# 1-Schematic_2-IRT-GR4-ColleJoulian.net
KiCad netlist of a schematic drawn in EasyEDA
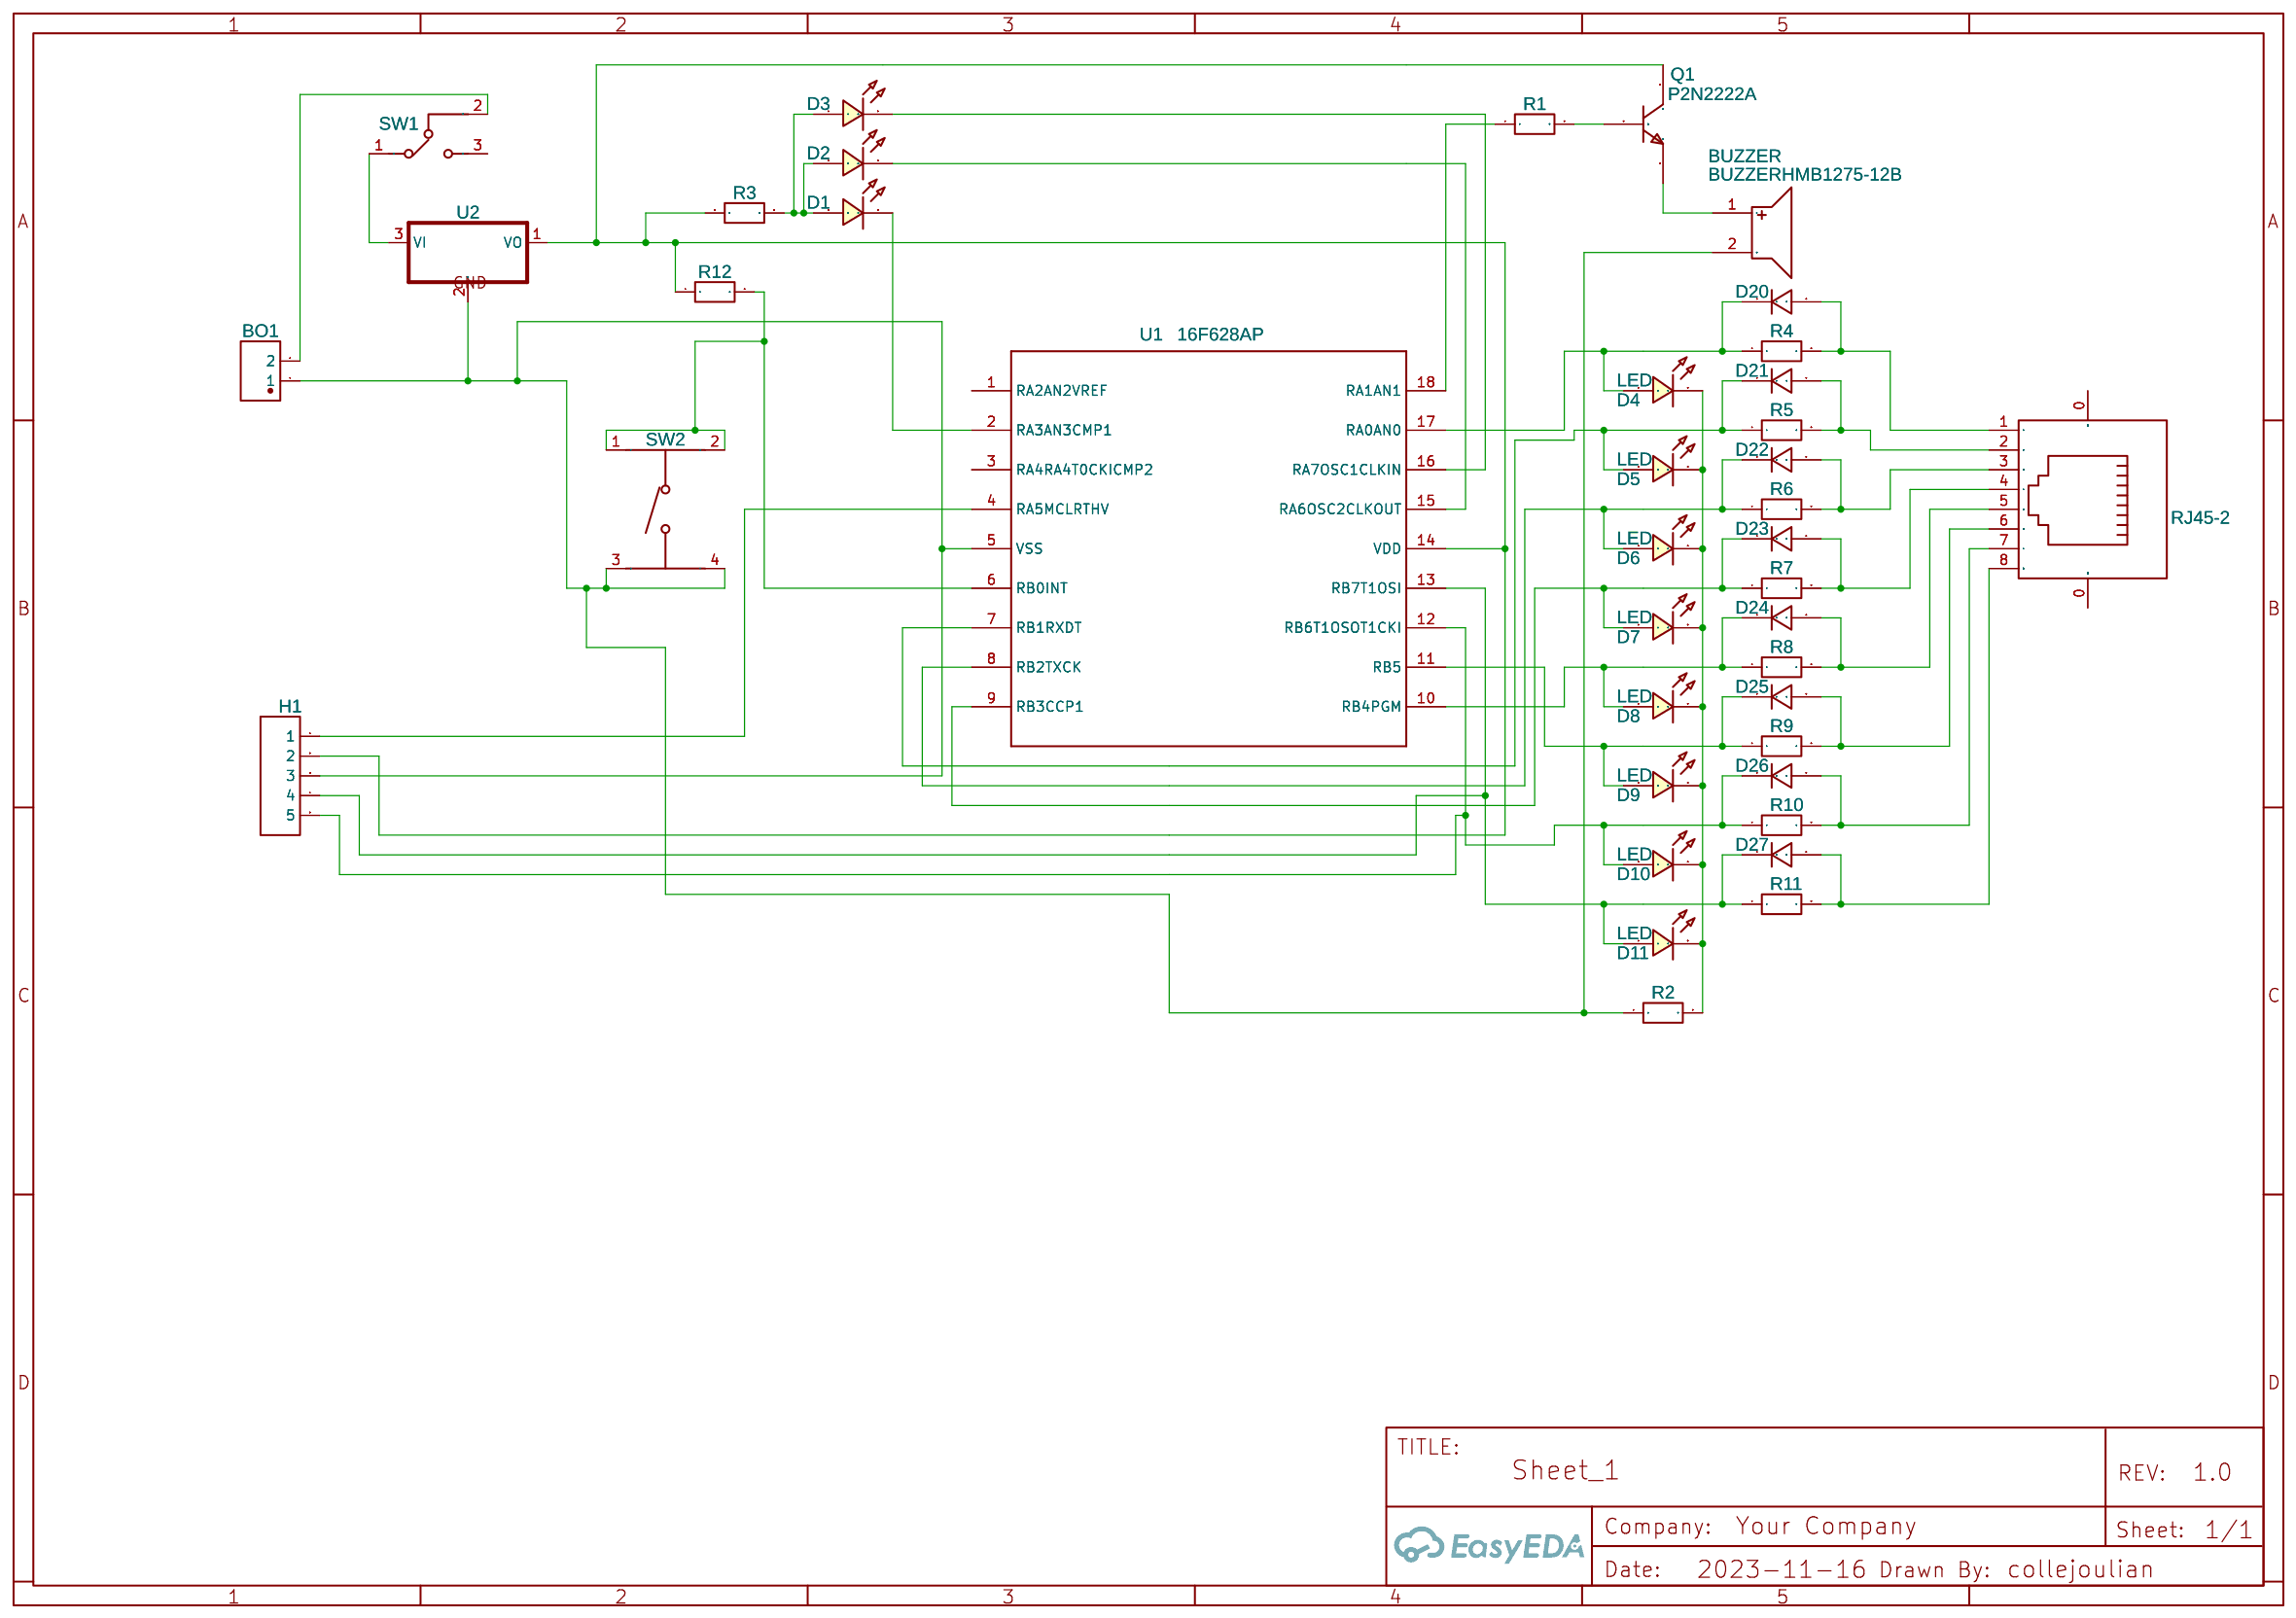
[diagram p0: schematic sheet]

(export (version "E")
  (design (tool "Eeschema 10.0.6"))
  (components
    (comp (ref "BO1")
      (value "BV-2P-5mm")
      (fields
        (field (name "Manufacturer Part") "KF301-5.0-2P")
        (field (name "Manufacturer") "Cixi Kefa Elec")
      )
      (libsource (lib "") (part "Bornier A Vis 2P - 5mm"))
    )
    (comp (ref "BUZZER")
      (value "BUZZERHMB1275-12B")
      (fields (field (name "Manufacturer Part") "buzzerHMB1275-12B") (field (name "Manufacturer") "HNDZ"))
      (libsource (lib "") (part "BUZZERHMB1275-12B"))
    )
    (comp (ref "D1")
      (value "D1")
      (fields
        (field (name "Manufacturer Part") "204-10SDRD/S530-A3-L")
        (field (name "Manufacturer") "EVERLIGHT(台湾亿光)")
      )
      (libsource (lib "") (part "LED-TH-3mm_R"))
    )
    (comp (ref "D2")
      (value "D2")
      (fields
        (field (name "Manufacturer Part") "204-10SDRD/S530-A3-L")
        (field (name "Manufacturer") "EVERLIGHT(台湾亿光)")
      )
      (libsource (lib "") (part "LED-TH-3mm_R"))
    )
    (comp (ref "D3")
      (value "D3")
      (fields
        (field (name "Manufacturer Part") "204-10SDRD/S530-A3-L")
        (field (name "Manufacturer") "EVERLIGHT(台湾亿光)")
      )
      (libsource (lib "") (part "LED-TH-3mm_R"))
    )
    (comp (ref "D4")
      (value "LED")
      (fields
        (field (name "Manufacturer Part") "204-10SDRD/S530-A3-L")
        (field (name "Manufacturer") "EVERLIGHT(台湾亿光)")
      )
      (libsource (lib "") (part "LED-TH-3mm_R"))
    )
    (comp (ref "D5")
      (value "LED")
      (fields
        (field (name "Manufacturer Part") "204-10SDRD/S530-A3-L")
        (field (name "Manufacturer") "EVERLIGHT(台湾亿光)")
      )
      (libsource (lib "") (part "LED-TH-3mm_R"))
    )
    (comp (ref "D6")
      (value "LED")
      (fields
        (field (name "Manufacturer Part") "204-10SDRD/S530-A3-L")
        (field (name "Manufacturer") "EVERLIGHT(台湾亿光)")
      )
      (libsource (lib "") (part "LED-TH-3mm_R"))
    )
    (comp (ref "D7")
      (value "LED")
      (fields
        (field (name "Manufacturer Part") "204-10SDRD/S530-A3-L")
        (field (name "Manufacturer") "EVERLIGHT(台湾亿光)")
      )
      (libsource (lib "") (part "LED-TH-3mm_R"))
    )
    (comp (ref "D8")
      (value "LED")
      (fields
        (field (name "Manufacturer Part") "204-10SDRD/S530-A3-L")
        (field (name "Manufacturer") "EVERLIGHT(台湾亿光)")
      )
      (libsource (lib "") (part "LED-TH-3mm_R"))
    )
    (comp (ref "D9")
      (value "LED")
      (fields
        (field (name "Manufacturer Part") "204-10SDRD/S530-A3-L")
        (field (name "Manufacturer") "EVERLIGHT(台湾亿光)")
      )
      (libsource (lib "") (part "LED-TH-3mm_R"))
    )
    (comp (ref "D10")
      (value "LED")
      (fields
        (field (name "Manufacturer Part") "204-10SDRD/S530-A3-L")
        (field (name "Manufacturer") "EVERLIGHT(台湾亿光)")
      )
      (libsource (lib "") (part "LED-TH-3mm_R"))
    )
    (comp (ref "D11")
      (value "LED")
      (fields
        (field (name "Manufacturer Part") "204-10SDRD/S530-A3-L")
        (field (name "Manufacturer") "EVERLIGHT(台湾亿光)")
      )
      (libsource (lib "") (part "LED-TH-3mm_R"))
    )
    (comp (ref "D20")
      (value "D")
      (fields (field (name "Manufacturer Part") "1N4148") (field (name "Manufacturer") "STMicroelectronics"))
      (libsource (lib "") (part "1N4148"))
    )
    (comp (ref "D21")
      (value "D")
      (fields (field (name "Manufacturer Part") "1N4148") (field (name "Manufacturer") "STMicroelectronics"))
      (libsource (lib "") (part "1N4148"))
    )
    (comp (ref "D22")
      (value "D")
      (fields (field (name "Manufacturer Part") "1N4148") (field (name "Manufacturer") "STMicroelectronics"))
      (libsource (lib "") (part "1N4148"))
    )
    (comp (ref "D23")
      (value "D")
      (fields (field (name "Manufacturer Part") "1N4148") (field (name "Manufacturer") "STMicroelectronics"))
      (libsource (lib "") (part "1N4148"))
    )
    (comp (ref "D24")
      (value "D")
      (fields (field (name "Manufacturer Part") "1N4148") (field (name "Manufacturer") "STMicroelectronics"))
      (libsource (lib "") (part "1N4148"))
    )
    (comp (ref "D25")
      (value "D")
      (fields (field (name "Manufacturer Part") "1N4148") (field (name "Manufacturer") "STMicroelectronics"))
      (libsource (lib "") (part "1N4148"))
    )
    (comp (ref "D26")
      (value "D")
      (fields (field (name "Manufacturer Part") "1N4148") (field (name "Manufacturer") "STMicroelectronics"))
      (libsource (lib "") (part "1N4148"))
    )
    (comp (ref "D27")
      (value "D")
      (fields (field (name "Manufacturer Part") "1N4148") (field (name "Manufacturer") "STMicroelectronics"))
      (libsource (lib "") (part "1N4148"))
    )
    (comp (ref "H1")
      (value "1z2")
      (fields (field (name "Manufacturer Part") "2.54-1*5P母") (field (name "Manufacturer") "BOOMELE(博穆精密)"))
      (libsource (lib "") (part "Header-Female-2.54_1x5"))
    )
    (comp (ref "Q1") (value "P2N2222A") (libsource (lib "") (part "P2N2222A")))
    (comp (ref "R1") (value "1k") (libsource (lib "") (part "R_AXIAL-0.3_EU")))
    (comp (ref "R2") (value "1k") (libsource (lib "") (part "R_AXIAL-0.3_EU")))
    (comp (ref "R3") (value "1k") (libsource (lib "") (part "R_AXIAL-0.3_EU")))
    (comp (ref "R4") (value "1k") (libsource (lib "") (part "R_AXIAL-0.3_EU")))
    (comp (ref "R5") (value "1k") (libsource (lib "") (part "R_AXIAL-0.3_EU")))
    (comp (ref "R6") (value "1k") (libsource (lib "") (part "R_AXIAL-0.3_EU")))
    (comp (ref "R7") (value "1k") (libsource (lib "") (part "R_AXIAL-0.3_EU")))
    (comp (ref "R8") (value "1k") (libsource (lib "") (part "R_AXIAL-0.3_EU")))
    (comp (ref "R9") (value "1k") (libsource (lib "") (part "R_AXIAL-0.3_EU")))
    (comp (ref "R10") (value "1k") (libsource (lib "") (part "R_AXIAL-0.3_EU")))
    (comp (ref "R11") (value "1k") (libsource (lib "") (part "R_AXIAL-0.3_EU")))
    (comp (ref "R12") (value "1k") (libsource (lib "") (part "R_AXIAL-0.3_EU")))
    (comp (ref "RJ45")
      (value "RJ45-2")
      (fields (field (name "Manufacturer Part") "DS1128-04-S8B8P-X") (field (name "Manufacturer") "CONNFLY"))
      (libsource (lib "") (part "DS1128-04-S8B8P-X"))
    )
    (comp (ref "SW1")
      (value "SW1")
      (fields (field (name "Manufacturer Part") "1101M2S3CQE2") (field (name "Manufacturer") "C&K"))
      (libsource (lib "") (part "1101M2S3CQE2"))
    )
    (comp (ref "SW2")
      (value "TS-1102-5016")
      (fields (field (name "Manufacturer") "SOFNG(硕方)"))
      (libsource (lib "") (part "TS-1102-5016"))
    )
    (comp (ref "U1") (value "16F628AP") (libsource (lib "") (part "16F628AP")))
    (comp (ref "U2") (value "7805L") (libsource (lib "") (part "7805L")))
  )
  (nets
    (net (code "1") (name "Net-(BO1-Pad2)") (class "Default")
      (node (ref "BO1") (pin "2") (pinfunction "2_2") (pintype "unspecified"))
      (node (ref "SW1") (pin "2") (pinfunction "2_2") (pintype "unspecified"))
    )
    (net (code "2") (name "Net-(D1-Pad1)") (class "Default")
      (node (ref "D1") (pin "1") (pinfunction "1_1") (pintype "unspecified"))
      (node (ref "D2") (pin "1") (pinfunction "1_1") (pintype "unspecified"))
      (node (ref "D3") (pin "1") (pinfunction "1_1") (pintype "unspecified"))
      (node (ref "R3") (pin "2") (pinfunction "2_2") (pintype "unspecified"))
    )
    (net (code "3") (name "Net-(D10-Pad2)") (class "Default")
      (node (ref "D10") (pin "2") (pinfunction "2_2") (pintype "unspecified"))
      (node (ref "D11") (pin "2") (pinfunction "2_2") (pintype "unspecified"))
      (node (ref "D4") (pin "2") (pinfunction "2_2") (pintype "unspecified"))
      (node (ref "D5") (pin "2") (pinfunction "2_2") (pintype "unspecified"))
      (node (ref "D6") (pin "2") (pinfunction "2_2") (pintype "unspecified"))
      (node (ref "D7") (pin "2") (pinfunction "2_2") (pintype "unspecified"))
      (node (ref "D8") (pin "2") (pinfunction "2_2") (pintype "unspecified"))
      (node (ref "D9") (pin "2") (pinfunction "2_2") (pintype "unspecified"))
      (node (ref "R2") (pin "2") (pinfunction "2_2") (pintype "unspecified"))
    )
    (net (code "4") (name "Net-(D20-Pad2)") (class "Default")
      (node (ref "D20") (pin "2") (pinfunction "2_2") (pintype "unspecified"))
      (node (ref "R4") (pin "2") (pinfunction "2_2") (pintype "unspecified"))
      (node (ref "RJ45") (pin "1") (pinfunction "1_1") (pintype "unspecified"))
    )
    (net (code "5") (name "Net-(D21-Pad2)") (class "Default")
      (node (ref "D21") (pin "2") (pinfunction "2_2") (pintype "unspecified"))
      (node (ref "R5") (pin "2") (pinfunction "2_2") (pintype "unspecified"))
      (node (ref "RJ45") (pin "2") (pinfunction "2_2") (pintype "unspecified"))
    )
    (net (code "6") (name "Net-(D22-Pad2)") (class "Default")
      (node (ref "D22") (pin "2") (pinfunction "2_2") (pintype "unspecified"))
      (node (ref "R6") (pin "2") (pinfunction "2_2") (pintype "unspecified"))
      (node (ref "RJ45") (pin "3") (pinfunction "3_3") (pintype "unspecified"))
    )
    (net (code "7") (name "Net-(D23-Pad2)") (class "Default")
      (node (ref "D23") (pin "2") (pinfunction "2_2") (pintype "unspecified"))
      (node (ref "R7") (pin "2") (pinfunction "2_2") (pintype "unspecified"))
      (node (ref "RJ45") (pin "4") (pinfunction "4_4") (pintype "unspecified"))
    )
    (net (code "8") (name "Net-(D24-Pad2)") (class "Default")
      (node (ref "D24") (pin "2") (pinfunction "2_2") (pintype "unspecified"))
      (node (ref "R8") (pin "2") (pinfunction "2_2") (pintype "unspecified"))
      (node (ref "RJ45") (pin "5") (pinfunction "5_5") (pintype "unspecified"))
    )
    (net (code "9") (name "Net-(D25-Pad2)") (class "Default")
      (node (ref "D25") (pin "2") (pinfunction "2_2") (pintype "unspecified"))
      (node (ref "R9") (pin "2") (pinfunction "2_2") (pintype "unspecified"))
      (node (ref "RJ45") (pin "6") (pinfunction "6_6") (pintype "unspecified"))
    )
    (net (code "10") (name "Net-(D26-Pad2)") (class "Default")
      (node (ref "D26") (pin "2") (pinfunction "2_2") (pintype "unspecified"))
      (node (ref "R10") (pin "2") (pinfunction "2_2") (pintype "unspecified"))
      (node (ref "RJ45") (pin "7") (pinfunction "7_7") (pintype "unspecified"))
    )
    (net (code "11") (name "Net-(D27-Pad2)") (class "Default")
      (node (ref "D27") (pin "2") (pinfunction "2_2") (pintype "unspecified"))
      (node (ref "R11") (pin "2") (pinfunction "2_2") (pintype "unspecified"))
      (node (ref "RJ45") (pin "8") (pinfunction "8_8") (pintype "unspecified"))
    )
    (net (code "12") (name "Net-(Q1-B)") (class "Default")
      (node (ref "Q1") (pin "2") (pinfunction "B_2") (pintype "unspecified"))
      (node (ref "R1") (pin "2") (pinfunction "2_2") (pintype "unspecified"))
    )
    (net (code "13") (name "Net-(Q1-C)") (class "Default")
      (node (ref "H1") (pin "2") (pinfunction "2_2") (pintype "input"))
      (node (ref "Q1") (pin "1") (pinfunction "C_1") (pintype "unspecified"))
      (node (ref "R12") (pin "1") (pinfunction "1_1") (pintype "unspecified"))
      (node (ref "R3") (pin "1") (pinfunction "1_1") (pintype "unspecified"))
      (node (ref "U1") (pin "14") (pinfunction "VDD_14") (pintype "passive"))
      (node (ref "U2") (pin "1") (pinfunction "VO_1") (pintype "unspecified"))
    )
    (net (code "14") (name "Net-(Q1-E)") (class "Default")
      (node (ref "BUZZER") (pin "1") (pinfunction "1_1") (pintype "unspecified"))
      (node (ref "Q1") (pin "3") (pinfunction "E_3") (pintype "unspecified"))
    )
    (net (code "15") (name "Net-(U1-RA0AN0)") (class "Default")
      (node (ref "D20") (pin "1") (pinfunction "1_1") (pintype "unspecified"))
      (node (ref "D4") (pin "1") (pinfunction "1_1") (pintype "unspecified"))
      (node (ref "R4") (pin "1") (pinfunction "1_1") (pintype "unspecified"))
      (node (ref "U1") (pin "17") (pinfunction "RA0AN0_17") (pintype "unspecified"))
    )
    (net (code "16") (name "Net-(U1-RA1AN1)") (class "Default")
      (node (ref "R1") (pin "1") (pinfunction "1_1") (pintype "unspecified"))
      (node (ref "U1") (pin "18") (pinfunction "RA1AN1_18") (pintype "unspecified"))
    )
    (net (code "17") (name "Net-(U1-RA3AN3CMP1)") (class "Default")
      (node (ref "D1") (pin "2") (pinfunction "2_2") (pintype "unspecified"))
      (node (ref "U1") (pin "2") (pinfunction "RA3AN3CMP1_2") (pintype "unspecified"))
    )
    (net (code "18") (name "Net-(U1-RA5MCLRTHV)") (class "Default")
      (node (ref "H1") (pin "1") (pinfunction "1_1") (pintype "input"))
      (node (ref "U1") (pin "4") (pinfunction "RA5MCLRTHV_4") (pintype "input"))
    )
    (net (code "19") (name "Net-(U1-RA6OSC2CLKOUT)") (class "Default")
      (node (ref "D2") (pin "2") (pinfunction "2_2") (pintype "unspecified"))
      (node (ref "U1") (pin "15") (pinfunction "RA6OSC2CLKOUT_15") (pintype "unspecified"))
    )
    (net (code "20") (name "Net-(U1-RA7OSC1CLKIN)") (class "Default")
      (node (ref "D3") (pin "2") (pinfunction "2_2") (pintype "unspecified"))
      (node (ref "U1") (pin "16") (pinfunction "RA7OSC1CLKIN_16") (pintype "unspecified"))
    )
    (net (code "21") (name "Net-(U1-RB0INT)") (class "Default")
      (node (ref "R12") (pin "2") (pinfunction "2_2") (pintype "unspecified"))
      (node (ref "SW2") (pin "1") (pinfunction "1_1") (pintype "unspecified"))
      (node (ref "SW2") (pin "2") (pinfunction "2_2") (pintype "unspecified"))
      (node (ref "U1") (pin "6") (pinfunction "RB0INT_6") (pintype "unspecified"))
    )
    (net (code "22") (name "Net-(U1-RB1RXDT)") (class "Default")
      (node (ref "D21") (pin "1") (pinfunction "1_1") (pintype "unspecified"))
      (node (ref "D5") (pin "1") (pinfunction "1_1") (pintype "unspecified"))
      (node (ref "R5") (pin "1") (pinfunction "1_1") (pintype "unspecified"))
      (node (ref "U1") (pin "7") (pinfunction "RB1RXDT_7") (pintype "unspecified"))
    )
    (net (code "23") (name "Net-(U1-RB2TXCK)") (class "Default")
      (node (ref "D22") (pin "1") (pinfunction "1_1") (pintype "unspecified"))
      (node (ref "D6") (pin "1") (pinfunction "1_1") (pintype "unspecified"))
      (node (ref "R6") (pin "1") (pinfunction "1_1") (pintype "unspecified"))
      (node (ref "U1") (pin "8") (pinfunction "RB2TXCK_8") (pintype "unspecified"))
    )
    (net (code "24") (name "Net-(U1-RB3CCP1)") (class "Default")
      (node (ref "D23") (pin "1") (pinfunction "1_1") (pintype "unspecified"))
      (node (ref "D7") (pin "1") (pinfunction "1_1") (pintype "unspecified"))
      (node (ref "R7") (pin "1") (pinfunction "1_1") (pintype "unspecified"))
      (node (ref "U1") (pin "9") (pinfunction "RB3CCP1_9") (pintype "unspecified"))
    )
    (net (code "25") (name "Net-(U1-RB4PGM)") (class "Default")
      (node (ref "D24") (pin "1") (pinfunction "1_1") (pintype "unspecified"))
      (node (ref "D8") (pin "1") (pinfunction "1_1") (pintype "unspecified"))
      (node (ref "R8") (pin "1") (pinfunction "1_1") (pintype "unspecified"))
      (node (ref "U1") (pin "10") (pinfunction "RB4PGM_10") (pintype "unspecified"))
    )
    (net (code "26") (name "Net-(U1-RB5)") (class "Default")
      (node (ref "D25") (pin "1") (pinfunction "1_1") (pintype "unspecified"))
      (node (ref "D9") (pin "1") (pinfunction "1_1") (pintype "unspecified"))
      (node (ref "R9") (pin "1") (pinfunction "1_1") (pintype "unspecified"))
      (node (ref "U1") (pin "11") (pinfunction "RB5_11") (pintype "unspecified"))
    )
    (net (code "27") (name "Net-(U1-RB6T1OSOT1CKI)") (class "Default")
      (node (ref "D10") (pin "1") (pinfunction "1_1") (pintype "unspecified"))
      (node (ref "D26") (pin "1") (pinfunction "1_1") (pintype "unspecified"))
      (node (ref "H1") (pin "5") (pinfunction "5_5") (pintype "input"))
      (node (ref "R10") (pin "1") (pinfunction "1_1") (pintype "unspecified"))
      (node (ref "U1") (pin "12") (pinfunction "RB6T1OSOT1CKI_12") (pintype "unspecified"))
    )
    (net (code "28") (name "Net-(U1-RB7T1OSI)") (class "Default")
      (node (ref "D11") (pin "1") (pinfunction "1_1") (pintype "unspecified"))
      (node (ref "D27") (pin "1") (pinfunction "1_1") (pintype "unspecified"))
      (node (ref "H1") (pin "4") (pinfunction "4_4") (pintype "input"))
      (node (ref "R11") (pin "1") (pinfunction "1_1") (pintype "unspecified"))
      (node (ref "U1") (pin "13") (pinfunction "RB7T1OSI_13") (pintype "unspecified"))
    )
    (net (code "29") (name "Net-(U1-VSS)") (class "Default")
      (node (ref "BO1") (pin "1") (pinfunction "1_1") (pintype "unspecified"))
      (node (ref "BUZZER") (pin "2") (pinfunction "2_2") (pintype "unspecified"))
      (node (ref "H1") (pin "3") (pinfunction "3_3") (pintype "input"))
      (node (ref "R2") (pin "1") (pinfunction "1_1") (pintype "unspecified"))
      (node (ref "SW2") (pin "3") (pinfunction "3_3") (pintype "unspecified"))
      (node (ref "SW2") (pin "4") (pinfunction "4_4") (pintype "unspecified"))
      (node (ref "U1") (pin "5") (pinfunction "VSS_5") (pintype "passive"))
      (node (ref "U2") (pin "2") (pinfunction "GND_2") (pintype "unspecified"))
    )
    (net (code "30") (name "Net-(U2-VI)") (class "Default")
      (node (ref "SW1") (pin "1") (pinfunction "1_1") (pintype "unspecified"))
      (node (ref "U2") (pin "3") (pinfunction "VI_3") (pintype "input"))
    )
    (net (code "31") (name "unconnected-(RJ45-SHIELD-Pad0)") (class "Default")
      (node (ref "RJ45") (pin "0") (pinfunction "SHIELD_0") (pintype "unspecified"))
    )
    (net (code "32") (name "unconnected-(RJ45-SHIELD-Pad0)_1") (class "Default")
      (node (ref "RJ45") (pin "0") (pinfunction "SHIELD_0") (pintype "unspecified"))
    )
    (net (code "33") (name "unconnected-(SW1-Pad3)") (class "Default")
      (node (ref "SW1") (pin "3") (pinfunction "3_3") (pintype "unspecified"))
    )
    (net (code "34") (name "unconnected-(U1-RA2AN2VREF-Pad1)") (class "Default")
      (node (ref "U1") (pin "1") (pinfunction "RA2AN2VREF_1") (pintype "unspecified"))
    )
    (net (code "35") (name "unconnected-(U1-RA4RA4T0CKICMP2-Pad3)") (class "Default")
      (node (ref "U1") (pin "3") (pinfunction "RA4RA4T0CKICMP2_3") (pintype "unspecified"))
    )
  )
)
